# SCH_usb-hub_2025-11-09.net
KiCad netlist of a schematic drawn in EasyEDA
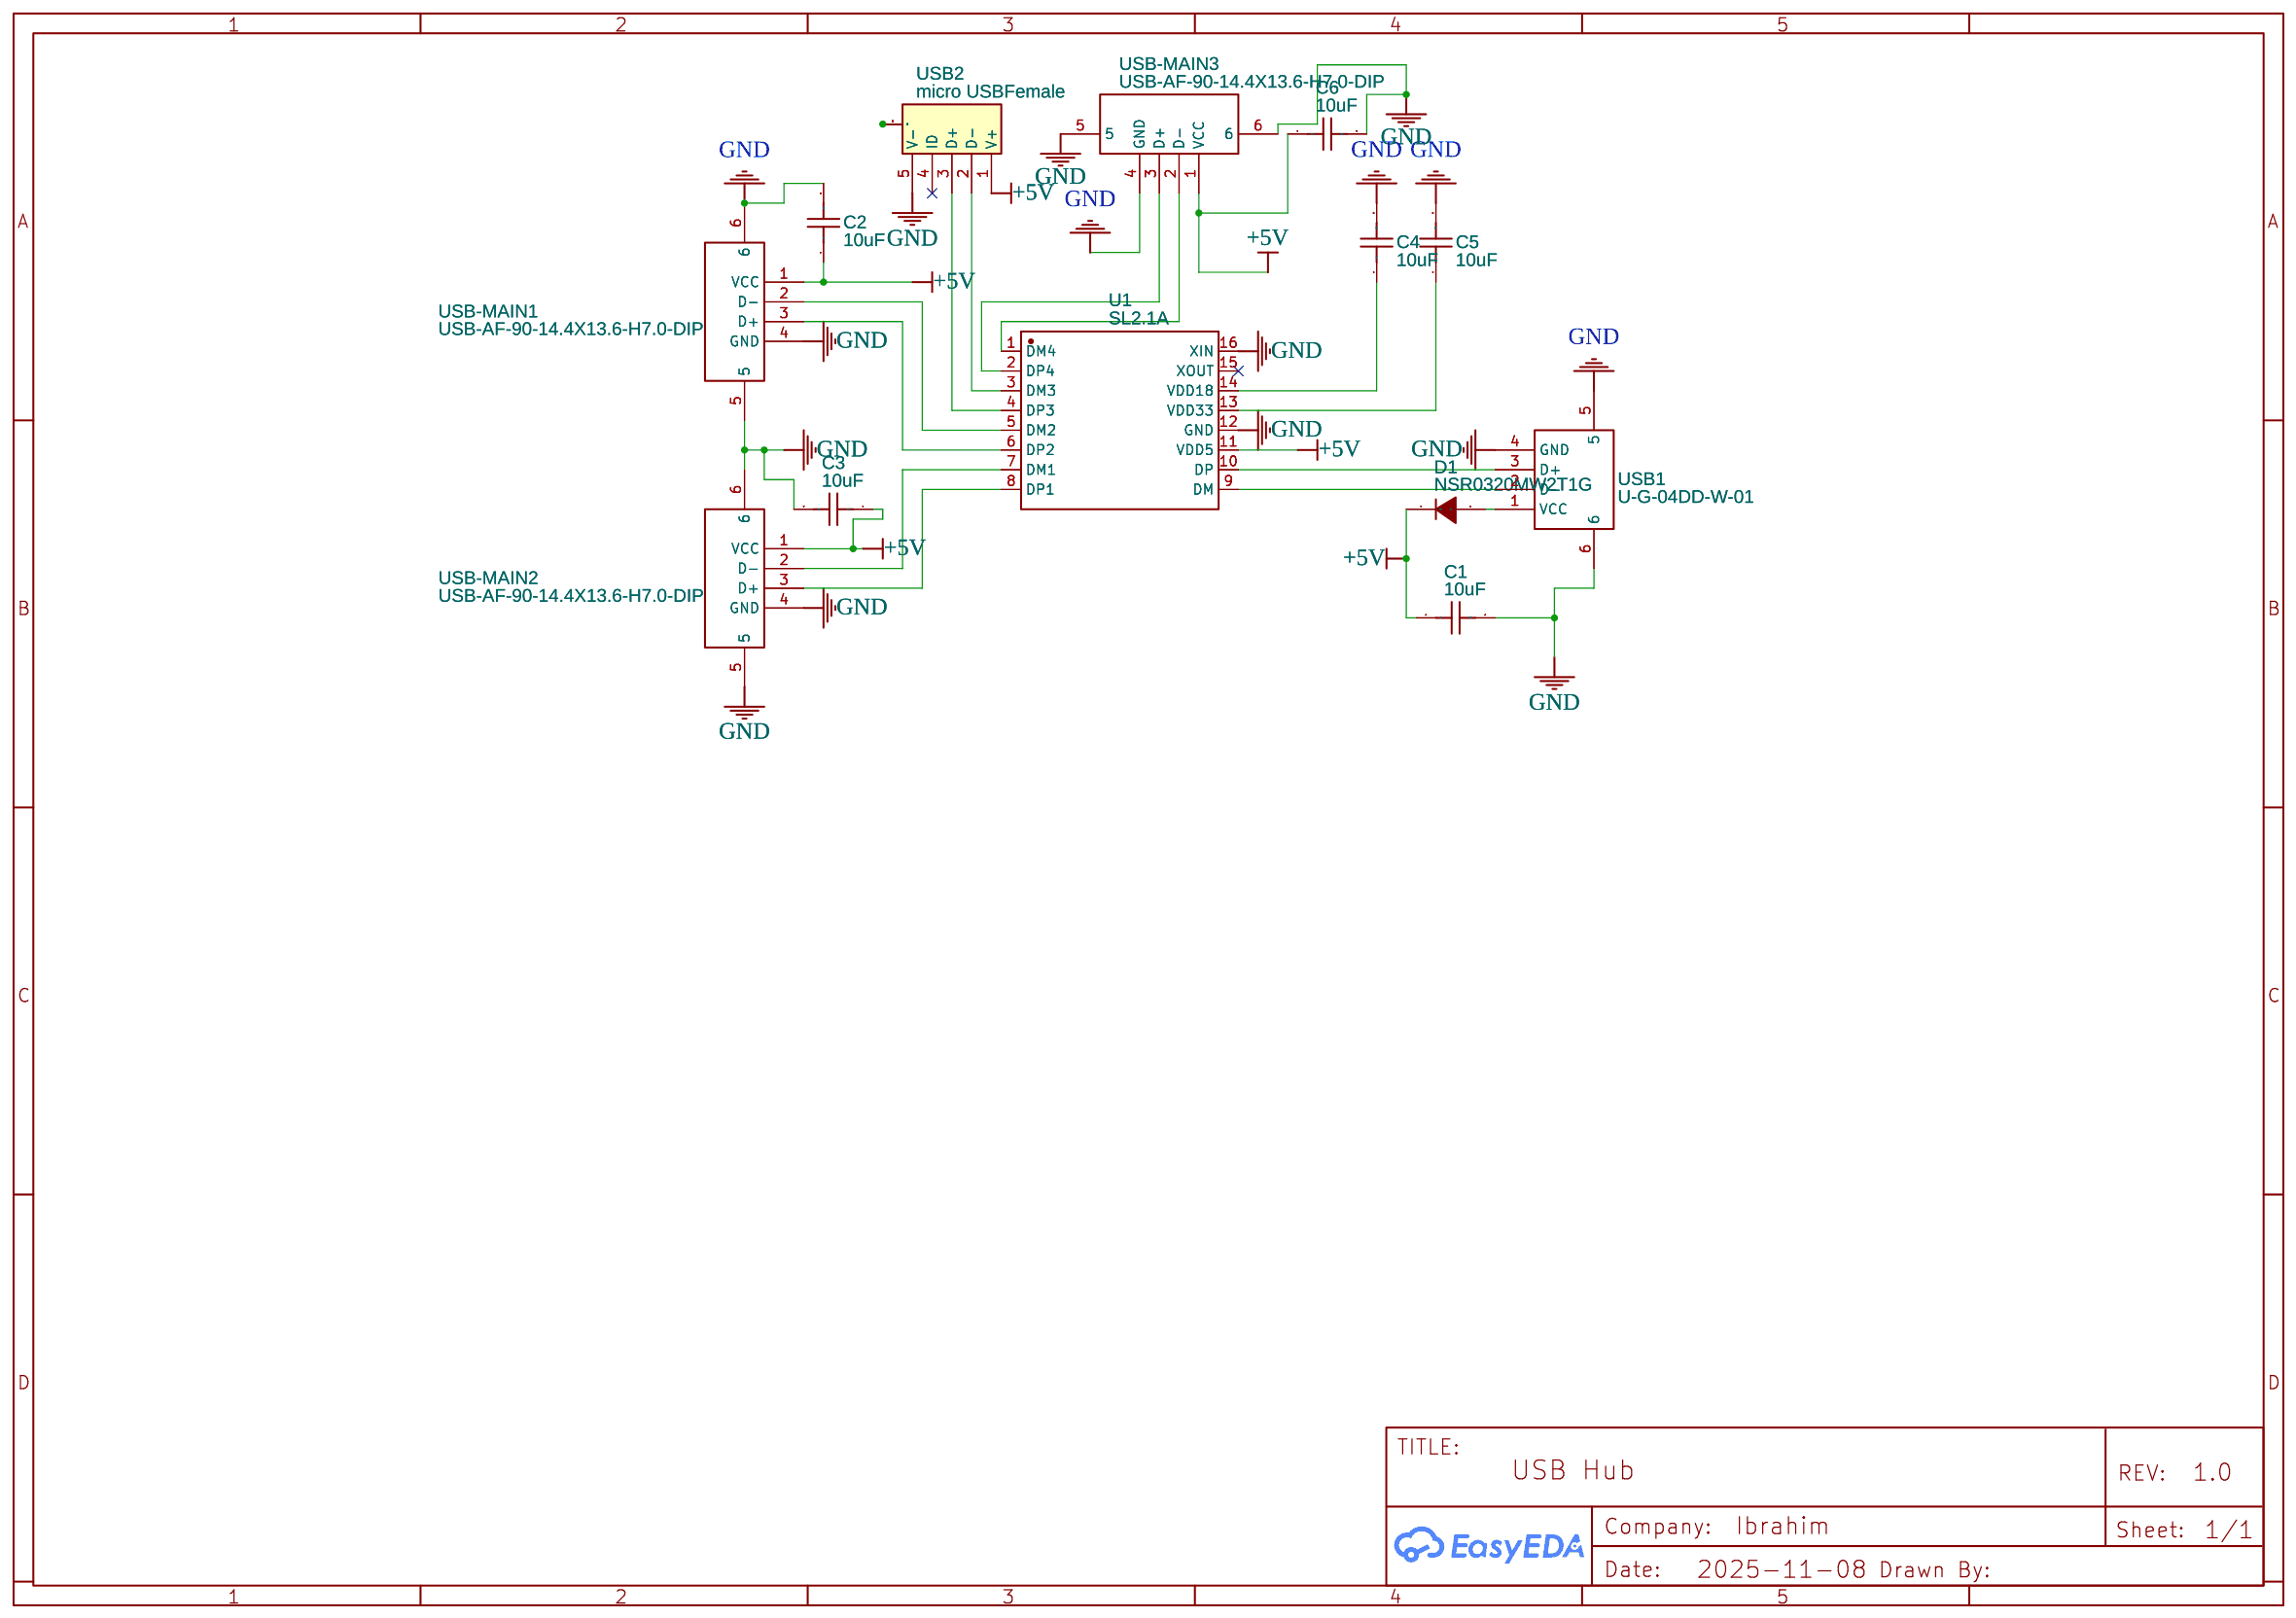
[diagram p0: schematic sheet]

(export (version "E")
  (design (tool "Eeschema 10.0.6"))
  (components
    (comp (ref "C1")
      (value "10uF")
      (fields
        (field (name "Manufacturer Part") "CL10A106KP8NNNC")
        (field (name "Manufacturer") "SAMSUNG(三星)")
      )
      (libsource (lib "") (part "CL10A106KP8NNNC_2"))
    )
    (comp (ref "C2")
      (value "10uF")
      (fields
        (field (name "Manufacturer Part") "CL10A106KP8NNNC")
        (field (name "Manufacturer") "SAMSUNG(三星)")
      )
      (libsource (lib "") (part "CL10A106KP8NNNC_1"))
    )
    (comp (ref "C3")
      (value "10uF")
      (fields
        (field (name "Manufacturer Part") "CL10A106KP8NNNC")
        (field (name "Manufacturer") "SAMSUNG(三星)")
      )
      (libsource (lib "") (part "CL10A106KP8NNNC"))
    )
    (comp (ref "C4")
      (value "10uF")
      (fields
        (field (name "Manufacturer Part") "CL10A106KP8NNNC")
        (field (name "Manufacturer") "SAMSUNG(三星)")
      )
      (libsource (lib "") (part "CL10A106KP8NNNC_1"))
    )
    (comp (ref "C5")
      (value "10uF")
      (fields
        (field (name "Manufacturer Part") "CL10A106KP8NNNC")
        (field (name "Manufacturer") "SAMSUNG(三星)")
      )
      (libsource (lib "") (part "CL10A106KP8NNNC_1"))
    )
    (comp (ref "C6")
      (value "10uF")
      (fields
        (field (name "Manufacturer Part") "CL10A106KP8NNNC")
        (field (name "Manufacturer") "SAMSUNG(三星)")
      )
      (libsource (lib "") (part "CL10A106KP8NNNC_2"))
    )
    (comp (ref "D1")
      (value "NSR0320MW2T1G")
      (fields (field (name "Manufacturer") "onsemi(安森美)"))
      (libsource (lib "") (part "NSR0320MW2T1G"))
    )
    (comp (ref "U1")
      (value "SL2.1A")
      (fields (field (name "Manufacturer") "CoreChips(和芯润德)"))
      (libsource (lib "") (part "SL2.1A"))
    )
    (comp (ref "USB-MAIN1")
      (value "USB-AF-90-14.4X13.6-H7.0-DIP")
      (fields (field (name "Manufacturer Part") "903-131A1011D10100") (field (name "Manufacturer") "精拓金"))
      (libsource (lib "") (part "USB-AF-90-14.4X13.6-H7.0-DIP"))
    )
    (comp (ref "USB-MAIN2")
      (value "USB-AF-90-14.4X13.6-H7.0-DIP")
      (fields (field (name "Manufacturer Part") "903-131A1011D10100") (field (name "Manufacturer") "精拓金"))
      (libsource (lib "") (part "USB-AF-90-14.4X13.6-H7.0-DIP"))
    )
    (comp (ref "USB-MAIN3")
      (value "USB-AF-90-14.4X13.6-H7.0-DIP")
      (fields (field (name "Manufacturer Part") "903-131A1011D10100") (field (name "Manufacturer") "精拓金"))
      (libsource (lib "") (part "USB-AF-90-14.4X13.6-H7.0-DIP_1"))
    )
    (comp (ref "USB1")
      (value "U-G-04DD-W-01")
      (fields (field (name "Manufacturer Part") "U-G-O4DD-W-1") (field (name "Manufacturer") "韩国韩荣"))
      (libsource (lib "") (part "U-G-04DD-W-01"))
    )
    (comp (ref "USB2")
      (value "micro USBFemale")
      (fields (field (name "Manufacturer Part") "920-E52A2021S10100") (field (name "Manufacturer") "精拓金"))
      (libsource (lib "") (part "micro USBFemale"))
    )
  )
  (nets
    (net (code "1") (name "+5V") (class "Default")
      (node (ref "C1") (pin "1") (pinfunction "1_1") (pintype "unspecified"))
      (node (ref "C2") (pin "1") (pinfunction "1_1") (pintype "unspecified"))
      (node (ref "C3") (pin "1") (pinfunction "1_1") (pintype "unspecified"))
      (node (ref "C6") (pin "1") (pinfunction "1_1") (pintype "unspecified"))
      (node (ref "D1") (pin "1") (pinfunction "C_1") (pintype "unspecified"))
      (node (ref "U1") (pin "11") (pinfunction "VDD5_11") (pintype "unspecified"))
      (node (ref "USB-MAIN1") (pin "1") (pinfunction "VCC_1") (pintype "unspecified"))
      (node (ref "USB-MAIN2") (pin "1") (pinfunction "VCC_1") (pintype "unspecified"))
      (node (ref "USB-MAIN3") (pin "1") (pinfunction "VCC_1") (pintype "unspecified"))
      (node (ref "USB2") (pin "1") (pinfunction "V+_1") (pintype "unspecified"))
    )
    (net (code "2") (name "GND") (class "Default")
      (node (ref "C1") (pin "2") (pinfunction "2_2") (pintype "unspecified"))
      (node (ref "C2") (pin "2") (pinfunction "2_2") (pintype "unspecified"))
      (node (ref "C3") (pin "2") (pinfunction "2_2") (pintype "unspecified"))
      (node (ref "C4") (pin "2") (pinfunction "2_2") (pintype "unspecified"))
      (node (ref "C5") (pin "2") (pinfunction "2_2") (pintype "unspecified"))
      (node (ref "C6") (pin "2") (pinfunction "2_2") (pintype "unspecified"))
      (node (ref "U1") (pin "12") (pinfunction "GND_12") (pintype "unspecified"))
      (node (ref "U1") (pin "16") (pinfunction "XIN_16") (pintype "unspecified"))
      (node (ref "USB-MAIN1") (pin "4") (pinfunction "GND_4") (pintype "unspecified"))
      (node (ref "USB-MAIN1") (pin "5") (pinfunction "5_5") (pintype "unspecified"))
      (node (ref "USB-MAIN1") (pin "6") (pinfunction "6_6") (pintype "unspecified"))
      (node (ref "USB-MAIN2") (pin "4") (pinfunction "GND_4") (pintype "unspecified"))
      (node (ref "USB-MAIN2") (pin "5") (pinfunction "5_5") (pintype "unspecified"))
      (node (ref "USB-MAIN2") (pin "6") (pinfunction "6_6") (pintype "unspecified"))
      (node (ref "USB-MAIN3") (pin "4") (pinfunction "GND_4") (pintype "unspecified"))
      (node (ref "USB-MAIN3") (pin "5") (pinfunction "5_5") (pintype "unspecified"))
      (node (ref "USB-MAIN3") (pin "6") (pinfunction "6_6") (pintype "unspecified"))
      (node (ref "USB1") (pin "4") (pinfunction "GND_4") (pintype "unspecified"))
      (node (ref "USB1") (pin "5") (pinfunction "5_5") (pintype "unspecified"))
      (node (ref "USB1") (pin "6") (pinfunction "6_6") (pintype "unspecified"))
      (node (ref "USB2") (pin "5") (pinfunction "V-_5") (pintype "unspecified"))
    )
    (net (code "3") (name "Net-(D1-A)") (class "Default")
      (node (ref "D1") (pin "2") (pinfunction "A_2") (pintype "unspecified"))
      (node (ref "USB1") (pin "1") (pinfunction "VCC_1") (pintype "unspecified"))
    )
    (net (code "4") (name "Net-(U1-DM)") (class "Default")
      (node (ref "U1") (pin "9") (pinfunction "DM_9") (pintype "unspecified"))
      (node (ref "USB1") (pin "2") (pinfunction "D-_2") (pintype "unspecified"))
    )
    (net (code "5") (name "Net-(U1-DM1)") (class "Default")
      (node (ref "U1") (pin "7") (pinfunction "DM1_7") (pintype "unspecified"))
      (node (ref "USB-MAIN2") (pin "2") (pinfunction "D-_2") (pintype "unspecified"))
    )
    (net (code "6") (name "Net-(U1-DM2)") (class "Default")
      (node (ref "U1") (pin "5") (pinfunction "DM2_5") (pintype "unspecified"))
      (node (ref "USB-MAIN1") (pin "2") (pinfunction "D-_2") (pintype "unspecified"))
    )
    (net (code "7") (name "Net-(U1-DM3)") (class "Default")
      (node (ref "U1") (pin "3") (pinfunction "DM3_3") (pintype "unspecified"))
      (node (ref "USB2") (pin "2") (pinfunction "D-_2") (pintype "unspecified"))
    )
    (net (code "8") (name "Net-(U1-DM4)") (class "Default")
      (node (ref "U1") (pin "1") (pinfunction "DM4_1") (pintype "unspecified"))
      (node (ref "USB-MAIN3") (pin "2") (pinfunction "D-_2") (pintype "unspecified"))
    )
    (net (code "9") (name "Net-(U1-DP)") (class "Default")
      (node (ref "U1") (pin "10") (pinfunction "DP_10") (pintype "unspecified"))
      (node (ref "USB1") (pin "3") (pinfunction "D+_3") (pintype "unspecified"))
    )
    (net (code "10") (name "Net-(U1-DP1)") (class "Default")
      (node (ref "U1") (pin "8") (pinfunction "DP1_8") (pintype "unspecified"))
      (node (ref "USB-MAIN2") (pin "3") (pinfunction "D+_3") (pintype "unspecified"))
    )
    (net (code "11") (name "Net-(U1-DP2)") (class "Default")
      (node (ref "U1") (pin "6") (pinfunction "DP2_6") (pintype "unspecified"))
      (node (ref "USB-MAIN1") (pin "3") (pinfunction "D+_3") (pintype "unspecified"))
    )
    (net (code "12") (name "Net-(U1-DP3)") (class "Default")
      (node (ref "U1") (pin "4") (pinfunction "DP3_4") (pintype "unspecified"))
      (node (ref "USB2") (pin "3") (pinfunction "D+_3") (pintype "unspecified"))
    )
    (net (code "13") (name "Net-(U1-DP4)") (class "Default")
      (node (ref "U1") (pin "2") (pinfunction "DP4_2") (pintype "unspecified"))
      (node (ref "USB-MAIN3") (pin "3") (pinfunction "D+_3") (pintype "unspecified"))
    )
    (net (code "14") (name "Net-(U1-VDD18)") (class "Default")
      (node (ref "C4") (pin "1") (pinfunction "1_1") (pintype "unspecified"))
      (node (ref "U1") (pin "14") (pinfunction "VDD18_14") (pintype "unspecified"))
    )
    (net (code "15") (name "Net-(U1-VDD33)") (class "Default")
      (node (ref "C5") (pin "1") (pinfunction "1_1") (pintype "unspecified"))
      (node (ref "U1") (pin "13") (pinfunction "VDD33_13") (pintype "unspecified"))
    )
    (net (code "16") (name "Net-(USB2-1)") (class "Default")
      (node (ref "USB2") (pin "SH0") (pinfunction "MTN_SH0") (pintype "input"))
      (node (ref "USB2") (pin "SH1") (pinfunction "1_SH1") (pintype "unspecified"))
      (node (ref "USB2") (pin "SH2") (pinfunction "2_SH2") (pintype "unspecified"))
      (node (ref "USB2") (pin "SH3") (pinfunction "3_SH3") (pintype "unspecified"))
    )
    (net (code "17") (name "unconnected-(U1-XOUT-Pad15)") (class "Default")
      (node (ref "U1") (pin "15") (pinfunction "XOUT_15") (pintype "unspecified+no_connect"))
    )
    (net (code "18") (name "unconnected-(USB2-ID-Pad4)") (class "Default")
      (node (ref "USB2") (pin "4") (pinfunction "ID_4") (pintype "unspecified+no_connect"))
    )
  )
)
